# solarpanel.net
KiCad netlist of a schematic drawn in EAGLE
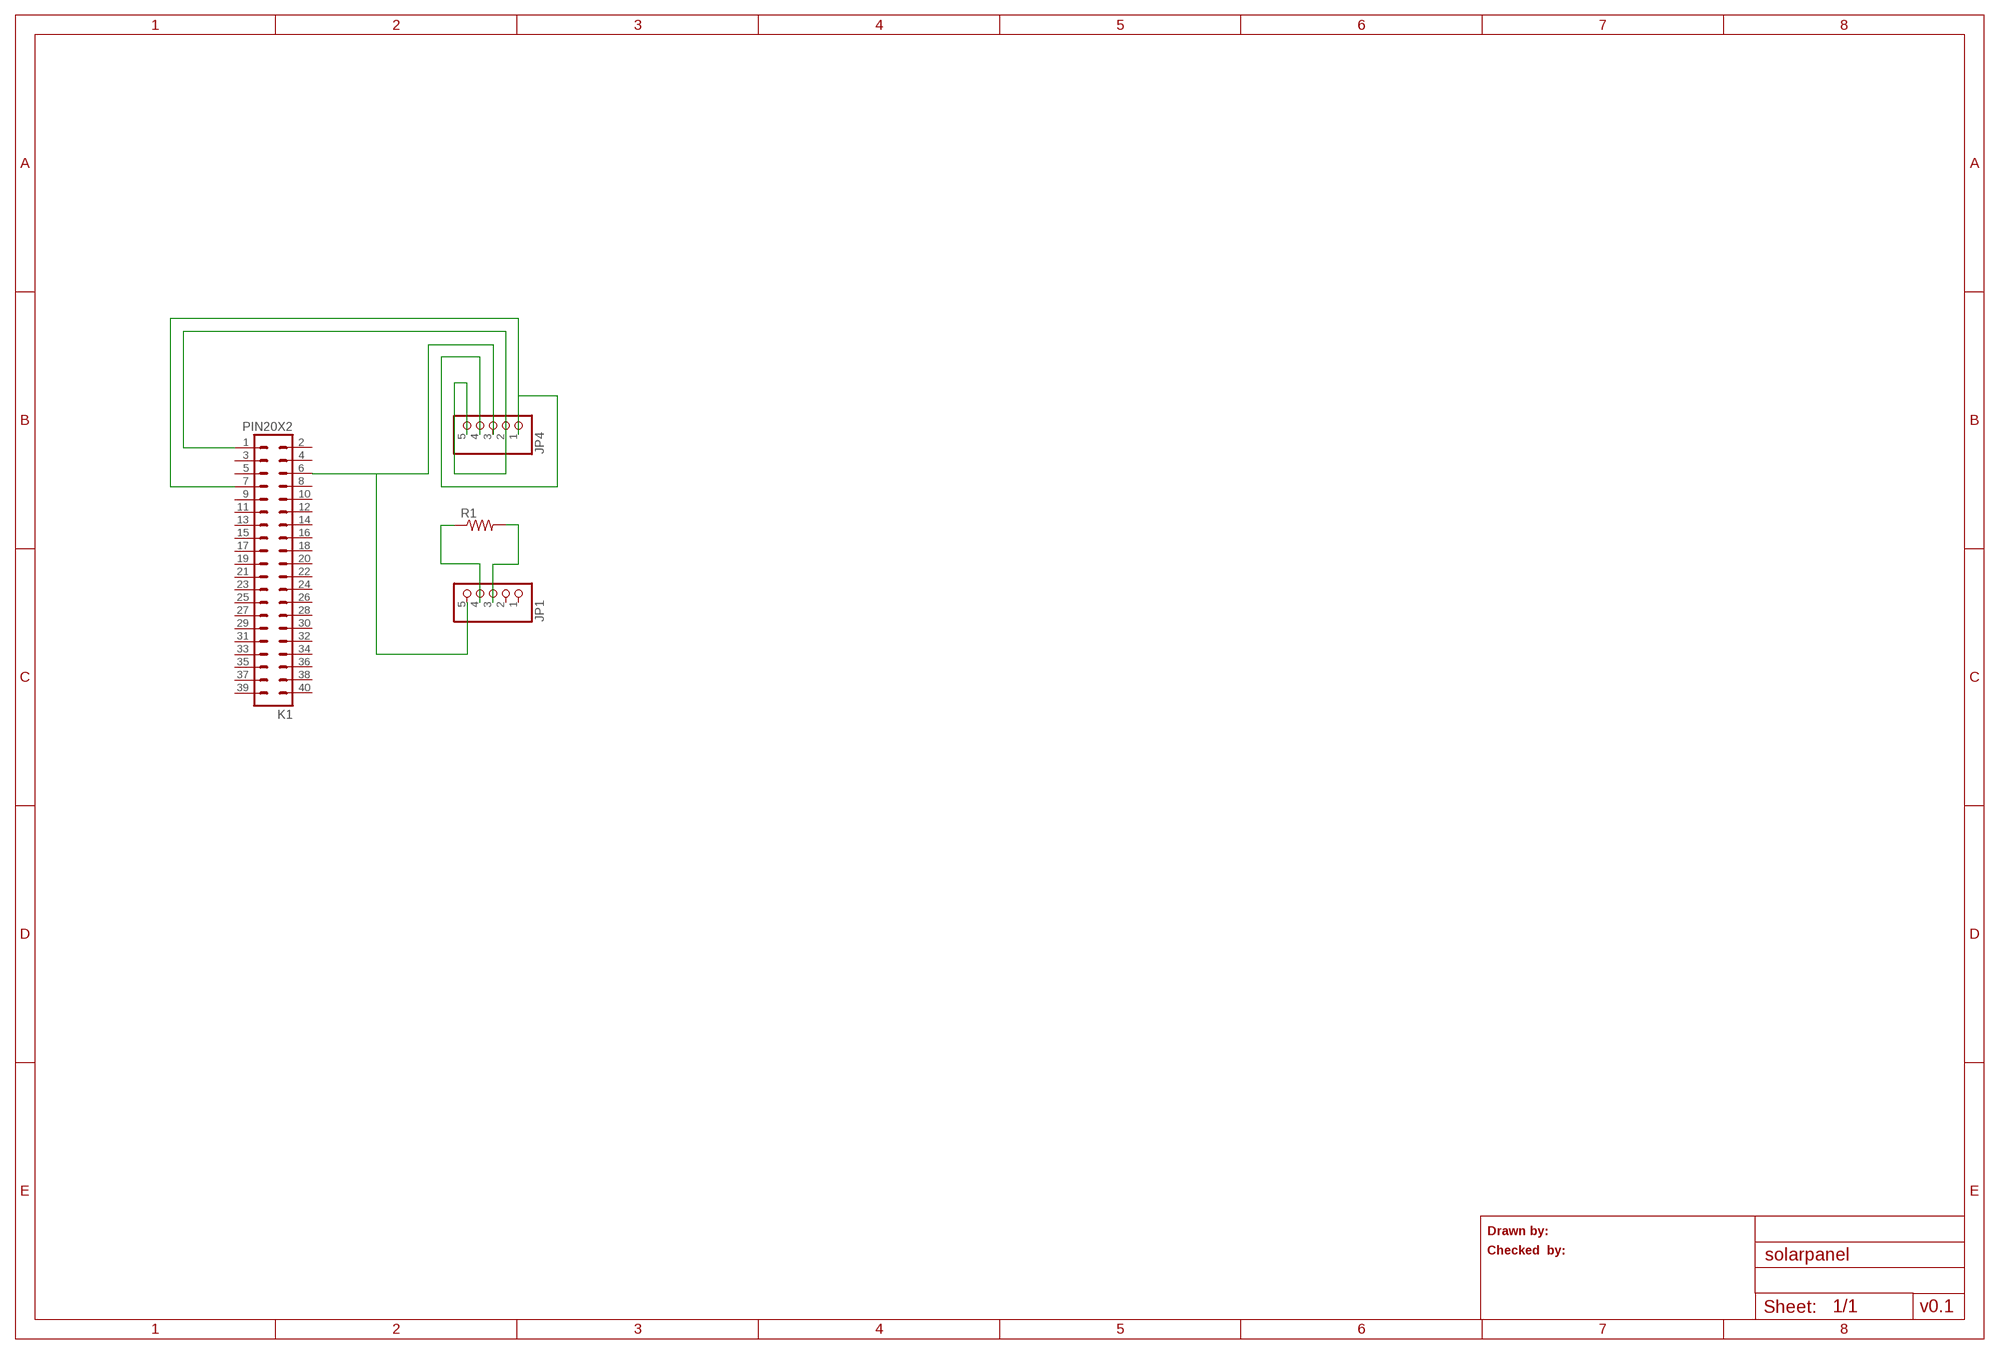
[diagram p0: schematic, sheet 1]

(export (version "E")
  (design (tool "Eeschema 10.0.6"))
  (components
    (comp (ref "JP1")
      (value "PINHD-1X5")
      (footprint "eagle-import:1X05")
      (libsource (lib "eagle-import") (part "PINHD-1X5"))
    )
    (comp (ref "JP4")
      (value "PINHD-1X5")
      (footprint "eagle-import:1X05")
      (libsource (lib "eagle-import") (part "PINHD-1X5"))
    )
    (comp (ref "K1")
      (value "PIN20X2")
      (footprint "eagle-import:PIN_20X2")
      (libsource (lib "eagle-import") (part "PIN20X2"))
    )
    (comp (ref "R1")
      (value "R-US_0207/10")
      (footprint "eagle-import:0207_10")
      (libsource (lib "eagle-import") (part "R-US_0207/10"))
    )
  )
  (nets
    (net (code "1") (name "Net-(JP1-Pad3)") (class "Default")
      (node (ref "JP1") (pin "3") (pinfunction "3_3") (pintype "passive"))
      (node (ref "R1") (pin "2") (pinfunction "2_2") (pintype "passive"))
    )
    (net (code "2") (name "Net-(JP1-Pad4)") (class "Default")
      (node (ref "JP1") (pin "4") (pinfunction "4_4") (pintype "passive"))
      (node (ref "R1") (pin "1") (pinfunction "1_1") (pintype "passive"))
    )
    (net (code "3") (name "Net-(JP1-Pad5)") (class "Default")
      (node (ref "JP1") (pin "5") (pinfunction "5_5") (pintype "passive"))
      (node (ref "JP4") (pin "3") (pinfunction "3_3") (pintype "passive"))
      (node (ref "K1") (pin "6") (pinfunction "6_6") (pintype "passive"))
    )
    (net (code "4") (name "Net-(JP4-Pad1)") (class "Default")
      (node (ref "JP4") (pin "1") (pinfunction "1_1") (pintype "passive"))
      (node (ref "JP4") (pin "4") (pinfunction "4_4") (pintype "passive"))
      (node (ref "K1") (pin "7") (pinfunction "7_7") (pintype "passive"))
    )
    (net (code "5") (name "Net-(JP4-Pad2)") (class "Default")
      (node (ref "JP4") (pin "2") (pinfunction "2_2") (pintype "passive"))
      (node (ref "JP4") (pin "5") (pinfunction "5_5") (pintype "passive"))
      (node (ref "K1") (pin "1") (pinfunction "1_1") (pintype "passive"))
    )
    (net (code "6") (name "unconnected-(JP1-Pad1)") (class "Default")
      (node (ref "JP1") (pin "1") (pinfunction "1_1") (pintype "passive"))
    )
    (net (code "7") (name "unconnected-(JP1-Pad2)") (class "Default")
      (node (ref "JP1") (pin "2") (pinfunction "2_2") (pintype "passive"))
    )
    (net (code "8") (name "unconnected-(K1-Pad2)") (class "Default")
      (node (ref "K1") (pin "2") (pinfunction "2_2") (pintype "passive"))
    )
    (net (code "9") (name "unconnected-(K1-Pad3)") (class "Default")
      (node (ref "K1") (pin "3") (pinfunction "3_3") (pintype "passive"))
    )
    (net (code "10") (name "unconnected-(K1-Pad4)") (class "Default")
      (node (ref "K1") (pin "4") (pinfunction "4_4") (pintype "passive"))
    )
    (net (code "11") (name "unconnected-(K1-Pad5)") (class "Default")
      (node (ref "K1") (pin "5") (pinfunction "5_5") (pintype "passive"))
    )
    (net (code "12") (name "unconnected-(K1-Pad8)") (class "Default")
      (node (ref "K1") (pin "8") (pinfunction "8_8") (pintype "passive"))
    )
    (net (code "13") (name "unconnected-(K1-Pad9)") (class "Default")
      (node (ref "K1") (pin "9") (pinfunction "9_9") (pintype "passive"))
    )
    (net (code "14") (name "unconnected-(K1-Pad10)") (class "Default")
      (node (ref "K1") (pin "10") (pinfunction "10_10") (pintype "passive"))
    )
    (net (code "15") (name "unconnected-(K1-Pad11)") (class "Default")
      (node (ref "K1") (pin "11") (pinfunction "11_11") (pintype "passive"))
    )
    (net (code "16") (name "unconnected-(K1-Pad12)") (class "Default")
      (node (ref "K1") (pin "12") (pinfunction "12_12") (pintype "passive"))
    )
    (net (code "17") (name "unconnected-(K1-Pad13)") (class "Default")
      (node (ref "K1") (pin "13") (pinfunction "13_13") (pintype "passive"))
    )
    (net (code "18") (name "unconnected-(K1-Pad14)") (class "Default")
      (node (ref "K1") (pin "14") (pinfunction "14_14") (pintype "passive"))
    )
    (net (code "19") (name "unconnected-(K1-Pad15)") (class "Default")
      (node (ref "K1") (pin "15") (pinfunction "15_15") (pintype "passive"))
    )
    (net (code "20") (name "unconnected-(K1-Pad16)") (class "Default")
      (node (ref "K1") (pin "16") (pinfunction "16_16") (pintype "passive"))
    )
    (net (code "21") (name "unconnected-(K1-Pad17)") (class "Default")
      (node (ref "K1") (pin "17") (pinfunction "17_17") (pintype "passive"))
    )
    (net (code "22") (name "unconnected-(K1-Pad18)") (class "Default")
      (node (ref "K1") (pin "18") (pinfunction "18_18") (pintype "passive"))
    )
    (net (code "23") (name "unconnected-(K1-Pad19)") (class "Default")
      (node (ref "K1") (pin "19") (pinfunction "19_19") (pintype "passive"))
    )
    (net (code "24") (name "unconnected-(K1-Pad20)") (class "Default")
      (node (ref "K1") (pin "20") (pinfunction "20_20") (pintype "passive"))
    )
    (net (code "25") (name "unconnected-(K1-Pad21)") (class "Default")
      (node (ref "K1") (pin "21") (pinfunction "21_21") (pintype "passive"))
    )
    (net (code "26") (name "unconnected-(K1-Pad22)") (class "Default")
      (node (ref "K1") (pin "22") (pinfunction "22_22") (pintype "passive"))
    )
    (net (code "27") (name "unconnected-(K1-Pad23)") (class "Default")
      (node (ref "K1") (pin "23") (pinfunction "23_23") (pintype "passive"))
    )
    (net (code "28") (name "unconnected-(K1-Pad24)") (class "Default")
      (node (ref "K1") (pin "24") (pinfunction "24_24") (pintype "passive"))
    )
    (net (code "29") (name "unconnected-(K1-Pad25)") (class "Default")
      (node (ref "K1") (pin "25") (pinfunction "25_25") (pintype "passive"))
    )
    (net (code "30") (name "unconnected-(K1-Pad26)") (class "Default")
      (node (ref "K1") (pin "26") (pinfunction "26_26") (pintype "passive"))
    )
    (net (code "31") (name "unconnected-(K1-Pad27)") (class "Default")
      (node (ref "K1") (pin "27") (pinfunction "27_27") (pintype "passive"))
    )
    (net (code "32") (name "unconnected-(K1-Pad28)") (class "Default")
      (node (ref "K1") (pin "28") (pinfunction "28_28") (pintype "passive"))
    )
    (net (code "33") (name "unconnected-(K1-Pad29)") (class "Default")
      (node (ref "K1") (pin "29") (pinfunction "29_29") (pintype "passive"))
    )
    (net (code "34") (name "unconnected-(K1-Pad30)") (class "Default")
      (node (ref "K1") (pin "30") (pinfunction "30_30") (pintype "passive"))
    )
    (net (code "35") (name "unconnected-(K1-Pad31)") (class "Default")
      (node (ref "K1") (pin "31") (pinfunction "31_31") (pintype "passive"))
    )
    (net (code "36") (name "unconnected-(K1-Pad32)") (class "Default")
      (node (ref "K1") (pin "32") (pinfunction "32_32") (pintype "passive"))
    )
    (net (code "37") (name "unconnected-(K1-Pad33)") (class "Default")
      (node (ref "K1") (pin "33") (pinfunction "33_33") (pintype "passive"))
    )
    (net (code "38") (name "unconnected-(K1-Pad34)") (class "Default")
      (node (ref "K1") (pin "34") (pinfunction "34_34") (pintype "passive"))
    )
    (net (code "39") (name "unconnected-(K1-Pad35)") (class "Default")
      (node (ref "K1") (pin "35") (pinfunction "35_35") (pintype "passive"))
    )
    (net (code "40") (name "unconnected-(K1-Pad36)") (class "Default")
      (node (ref "K1") (pin "36") (pinfunction "36_36") (pintype "passive"))
    )
    (net (code "41") (name "unconnected-(K1-Pad37)") (class "Default")
      (node (ref "K1") (pin "37") (pinfunction "37_37") (pintype "passive"))
    )
    (net (code "42") (name "unconnected-(K1-Pad38)") (class "Default")
      (node (ref "K1") (pin "38") (pinfunction "38_38") (pintype "passive"))
    )
    (net (code "43") (name "unconnected-(K1-Pad39)") (class "Default")
      (node (ref "K1") (pin "39") (pinfunction "39_39") (pintype "passive"))
    )
    (net (code "44") (name "unconnected-(K1-Pad40)") (class "Default")
      (node (ref "K1") (pin "40") (pinfunction "40_40") (pintype "passive"))
    )
  )
)
